# untitled.net
KiCad netlist of a schematic drawn in EAGLE
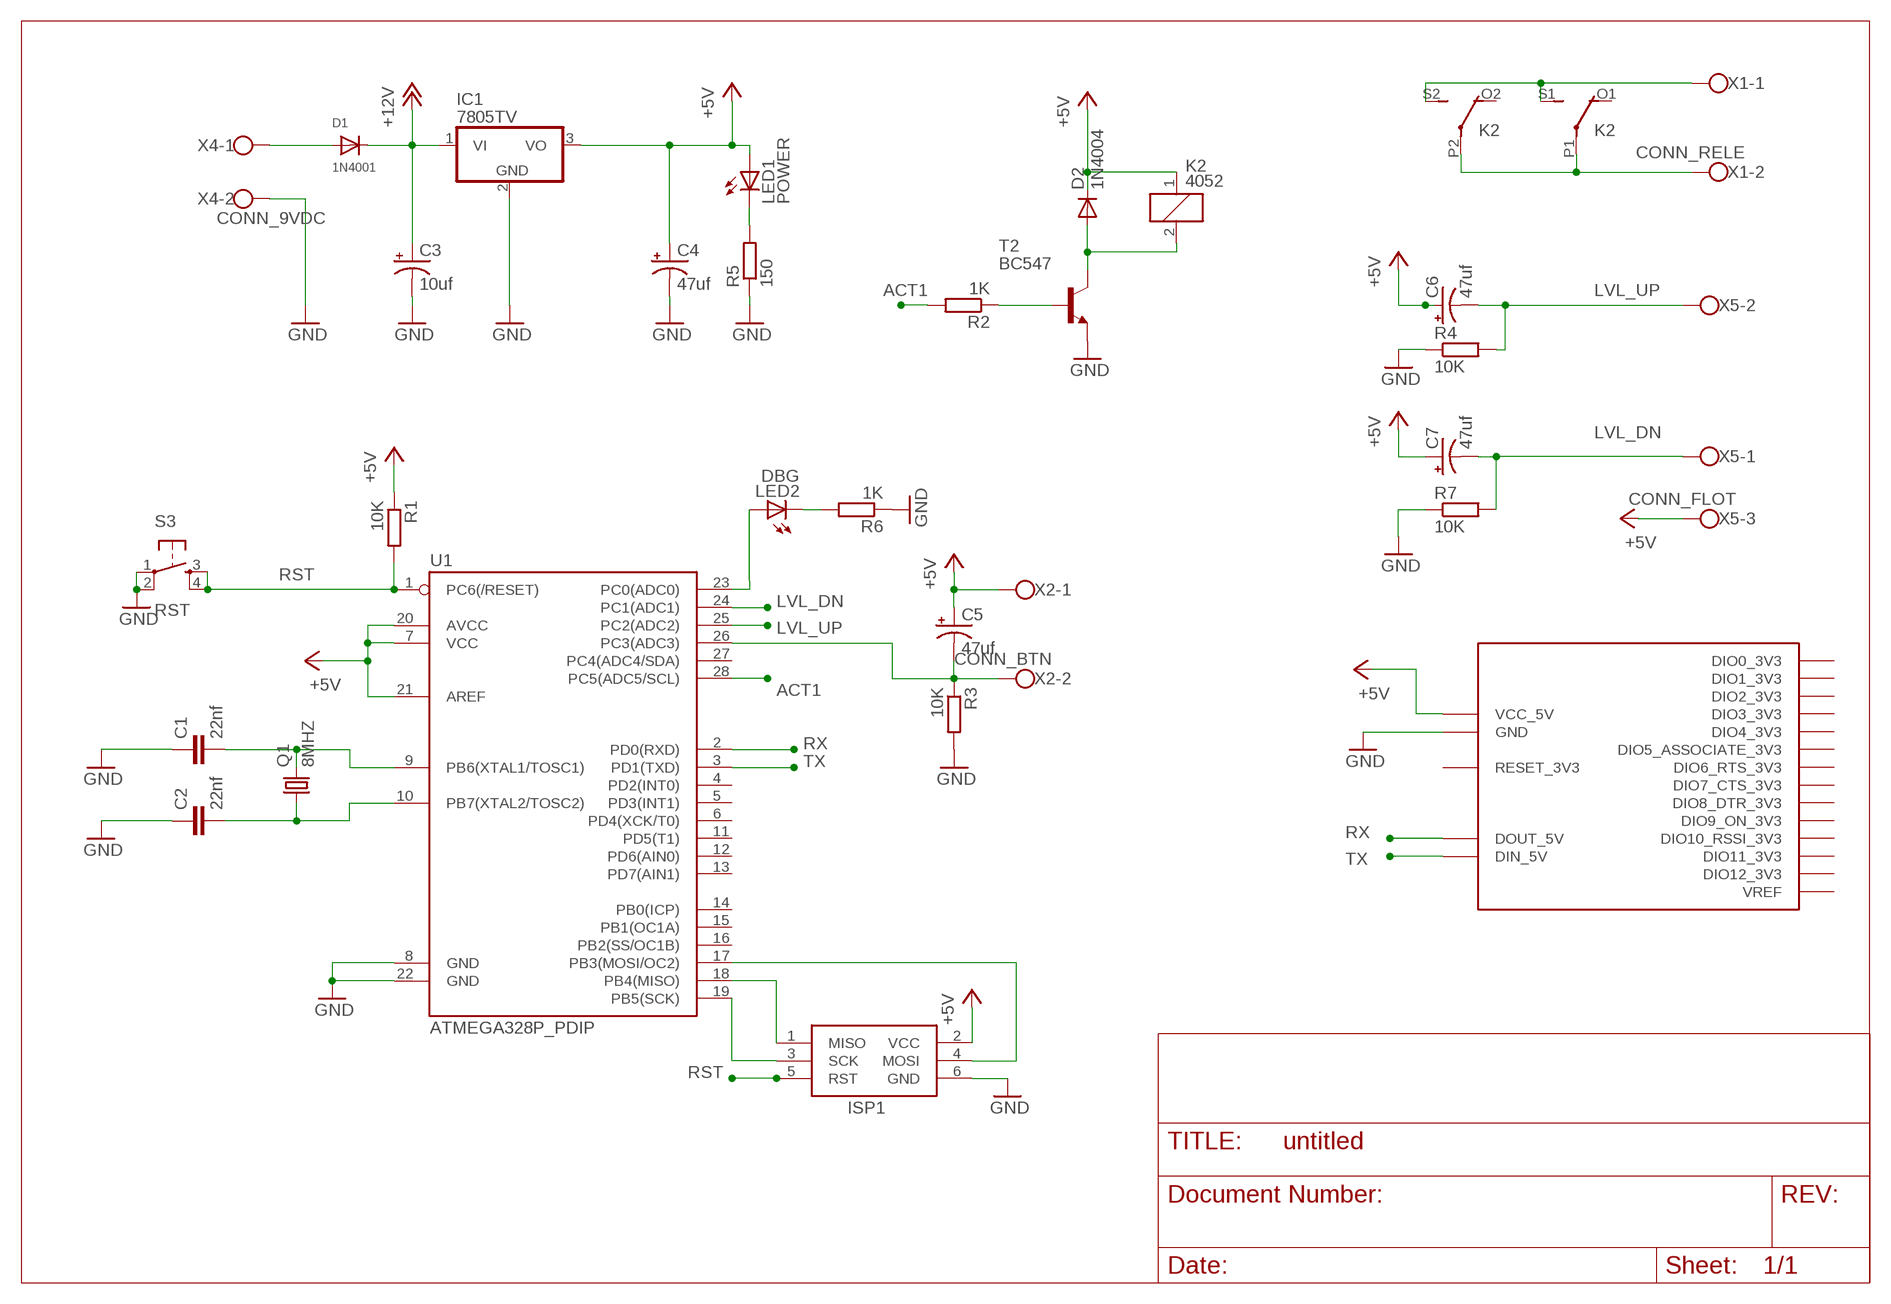
[diagram p0: schematic, sheet 1]

(export (version "E")
  (design (tool "Eeschema 10.0.6"))
  (components
    (comp (ref "C1")
      (value "22nf")
      (footprint "eagle-import:C2.5-3")
      (libsource (lib "eagle-import") (part "C2,5-3"))
    )
    (comp (ref "C2")
      (value "22nf")
      (footprint "eagle-import:C2.5-3")
      (libsource (lib "eagle-import") (part "C2,5-3"))
    )
    (comp (ref "C3")
      (value "10uf")
      (footprint "eagle-import:E2,5-6")
      (libsource (lib "eagle-import") (part "CPOL-USE2.5-6"))
    )
    (comp (ref "C4")
      (value "47uf")
      (footprint "eagle-import:E2,5-6")
      (libsource (lib "eagle-import") (part "CPOL-USE2.5-6"))
    )
    (comp (ref "C5")
      (value "47uf")
      (footprint "eagle-import:E2,5-6")
      (libsource (lib "eagle-import") (part "CPOL-USE2.5-6"))
    )
    (comp (ref "C6")
      (value "47uf")
      (footprint "eagle-import:E2,5-6")
      (libsource (lib "eagle-import") (part "CPOL-USE2.5-6"))
    )
    (comp (ref "C7")
      (value "47uf")
      (footprint "eagle-import:E2,5-6")
      (libsource (lib "eagle-import") (part "CPOL-USE2.5-6"))
    )
    (comp (ref "D1")
      (value "1N4001")
      (footprint "eagle-import:DO-1N4148")
      (libsource (lib "eagle-import") (part "DIODEDO-1N4148"))
    )
    (comp (ref "D2")
      (value "1N4004")
      (footprint "eagle-import:DO41-10")
      (libsource (lib "eagle-import") (part "1N4004"))
    )
    (comp (ref "IC1")
      (value "7805TV")
      (footprint "eagle-import:TO220V")
      (libsource (lib "eagle-import") (part "78TV05"))
    )
    (comp (ref "ISP1")
      (value "AVRISP-6")
      (footprint "eagle-import:AVRISP")
      (libsource (lib "eagle-import") (part "AVRISP-6"))
    )
    (comp (ref "K2")
      (value "4052")
      (footprint "eagle-import:F4052")
      (libsource (lib "eagle-import") (part "4052"))
    )
    (comp (ref "LED1")
      (value "POWER")
      (footprint "eagle-import:LED5MM")
      (libsource (lib "eagle-import") (part "LED5MM"))
    )
    (comp (ref "LED2")
      (value "DBG")
      (footprint "eagle-import:LED5MM")
      (libsource (lib "eagle-import") (part "LED5MM"))
    )
    (comp (ref "Q1")
      (value "8MHZ")
      (footprint "eagle-import:HC49U70")
      (libsource (lib "eagle-import") (part "CRYSTALHC49U70"))
    )
    (comp (ref "R1")
      (value "10K")
      (footprint "eagle-import:0207_10")
      (libsource (lib "eagle-import") (part "R-EU_0207/10"))
    )
    (comp (ref "R2")
      (value "1K")
      (footprint "eagle-import:0207_10")
      (libsource (lib "eagle-import") (part "R-EU_0207/10"))
    )
    (comp (ref "R3")
      (value "10K")
      (footprint "eagle-import:0207_10")
      (libsource (lib "eagle-import") (part "R-EU_0207/10"))
    )
    (comp (ref "R4")
      (value "10K")
      (footprint "eagle-import:0207_10")
      (libsource (lib "eagle-import") (part "R-EU_0207/10"))
    )
    (comp (ref "R5")
      (value "150")
      (footprint "eagle-import:0207_10")
      (libsource (lib "eagle-import") (part "R-EU_0207/10"))
    )
    (comp (ref "R6")
      (value "1K")
      (footprint "eagle-import:0207_10")
      (libsource (lib "eagle-import") (part "R-EU_0207/10"))
    )
    (comp (ref "R7")
      (value "10K")
      (footprint "eagle-import:0207_10")
      (libsource (lib "eagle-import") (part "R-EU_0207/10"))
    )
    (comp (ref "S3")
      (value "RST")
      (footprint "eagle-import:TACTILE-PTH")
      (libsource (lib "eagle-import") (part "TAC_SWITCHPTH"))
    )
    (comp (ref "T2")
      (value "BC547")
      (footprint "eagle-import:TO92-CBE")
      (libsource (lib "eagle-import") (part "-NPN-TO92-CBEBC547"))
    )
    (comp (ref "U$1")
      (value "XBEE_BREAKOUT_DIGOLE")
      (footprint "eagle-import:PDIP")
      (libsource (lib "eagle-import") (part "XBEE_BREAKOUT_DIGOLE"))
    )
    (comp (ref "U1")
      (value "ATMEGA328P_PDIP")
      (footprint "eagle-import:DIL28-3")
      (libsource (lib "eagle-import") (part "ATMEGA328P_PDIP"))
    )
    (comp (ref "X1")
      (value "CONN_RELE")
      (footprint "eagle-import:W237-102")
      (fields (field (name "MPN") "237-102"))
      (libsource (lib "eagle-import") (part "W237-102"))
    )
    (comp (ref "X2")
      (value "CONN_BTN")
      (footprint "eagle-import:W237-102")
      (fields (field (name "MPN") "237-102"))
      (libsource (lib "eagle-import") (part "W237-102"))
    )
    (comp (ref "X4")
      (value "CONN_9VDC")
      (footprint "eagle-import:W237-102")
      (fields (field (name "MPN") "237-102"))
      (libsource (lib "eagle-import") (part "W237-102"))
    )
    (comp (ref "X5")
      (value "CONN_FLOT")
      (footprint "eagle-import:W237-103")
      (fields (field (name "MPN") "237-103"))
      (libsource (lib "eagle-import") (part "W237-103"))
    )
  )
  (nets
    (net (code "1") (name "+5V") (class "Default")
      (node (ref "C4") (pin "+") (pinfunction "+_+") (pintype "passive"))
      (node (ref "C5") (pin "+") (pinfunction "+_+") (pintype "passive"))
      (node (ref "C6") (pin "+") (pinfunction "+_+") (pintype "passive"))
      (node (ref "C7") (pin "+") (pinfunction "+_+") (pintype "passive"))
      (node (ref "D2") (pin "C") (pinfunction "C_C") (pintype "passive"))
      (node (ref "IC1") (pin "3") (pinfunction "VO_3") (pintype "passive"))
      (node (ref "ISP1") (pin "2") (pinfunction "VCC_2") (pintype "power_in"))
      (node (ref "K2") (pin "1") (pinfunction "1_1") (pintype "passive"))
      (node (ref "LED1") (pin "A") (pinfunction "A_A") (pintype "passive"))
      (node (ref "R1") (pin "1") (pinfunction "1_1") (pintype "passive"))
      (node (ref "U$1") (pin "VCC_5V") (pinfunction "VCC_5V_VCC_5V") (pintype "bidirectional"))
      (node (ref "U1") (pin "20") (pinfunction "AVCC_20") (pintype "bidirectional"))
      (node (ref "U1") (pin "21") (pinfunction "AREF_21") (pintype "bidirectional"))
      (node (ref "U1") (pin "7") (pinfunction "VCC_7") (pintype "bidirectional"))
      (node (ref "X2") (pin "1") (pinfunction "KL_1") (pintype "passive"))
      (node (ref "X5") (pin "3") (pinfunction "KL_3") (pintype "passive"))
    )
    (net (code "2") (name "+12V") (class "Default")
      (node (ref "C3") (pin "+") (pinfunction "+_+") (pintype "passive"))
      (node (ref "D1") (pin "C") (pinfunction "C_C") (pintype "passive"))
      (node (ref "IC1") (pin "1") (pinfunction "VI_1") (pintype "input"))
    )
    (net (code "3") (name "/ACT1") (class "Default")
      (node (ref "R2") (pin "2") (pinfunction "2_2") (pintype "passive"))
      (node (ref "U1") (pin "28") (pinfunction "PC5(ADC5/SCL)_28") (pintype "bidirectional"))
    )
    (net (code "4") (name "/LVL_DN") (class "Default")
      (node (ref "C7") (pin "-") (pinfunction "-_-") (pintype "passive"))
      (node (ref "R7") (pin "2") (pinfunction "2_2") (pintype "passive"))
      (node (ref "U1") (pin "24") (pinfunction "PC1(ADC1)_24") (pintype "bidirectional"))
      (node (ref "X5") (pin "1") (pinfunction "KL_1") (pintype "passive"))
    )
    (net (code "5") (name "/LVL_UP") (class "Default")
      (node (ref "C6") (pin "-") (pinfunction "-_-") (pintype "passive"))
      (node (ref "R4") (pin "2") (pinfunction "2_2") (pintype "passive"))
      (node (ref "U1") (pin "25") (pinfunction "PC2(ADC2)_25") (pintype "bidirectional"))
      (node (ref "X5") (pin "2") (pinfunction "KL_2") (pintype "passive"))
    )
    (net (code "6") (name "/RST") (class "Default")
      (node (ref "ISP1") (pin "5") (pinfunction "RST_5") (pintype "output"))
      (node (ref "R1") (pin "2") (pinfunction "2_2") (pintype "passive"))
      (node (ref "S3") (pin "3") (pinfunction "3_3") (pintype "passive"))
      (node (ref "S3") (pin "4") (pinfunction "4_4") (pintype "passive"))
      (node (ref "U1") (pin "1") (pinfunction "PC6(/RESET)_1") (pintype "bidirectional"))
    )
    (net (code "7") (name "/RX") (class "Default")
      (node (ref "U$1") (pin "DOUT") (pinfunction "DOUT_5V_DOUT") (pintype "bidirectional"))
      (node (ref "U1") (pin "2") (pinfunction "PD0(RXD)_2") (pintype "bidirectional"))
    )
    (net (code "8") (name "/TX") (class "Default")
      (node (ref "U$1") (pin "DIN_5V") (pinfunction "DIN_5V_DIN_5V") (pintype "bidirectional"))
      (node (ref "U1") (pin "3") (pinfunction "PD1(TXD)_3") (pintype "bidirectional"))
    )
    (net (code "9") (name "GND") (class "Default")
      (node (ref "C1") (pin "1") (pinfunction "1_1") (pintype "passive"))
      (node (ref "C2") (pin "1") (pinfunction "1_1") (pintype "passive"))
      (node (ref "C3") (pin "-") (pinfunction "-_-") (pintype "passive"))
      (node (ref "C4") (pin "-") (pinfunction "-_-") (pintype "passive"))
      (node (ref "IC1") (pin "2") (pinfunction "GND_2") (pintype "passive"))
      (node (ref "ISP1") (pin "6") (pinfunction "GND_6") (pintype "power_in"))
      (node (ref "R3") (pin "2") (pinfunction "2_2") (pintype "passive"))
      (node (ref "R4") (pin "1") (pinfunction "1_1") (pintype "passive"))
      (node (ref "R5") (pin "1") (pinfunction "1_1") (pintype "passive"))
      (node (ref "R6") (pin "1") (pinfunction "1_1") (pintype "passive"))
      (node (ref "R7") (pin "1") (pinfunction "1_1") (pintype "passive"))
      (node (ref "S3") (pin "1") (pinfunction "1_1") (pintype "passive"))
      (node (ref "S3") (pin "2") (pinfunction "2_2") (pintype "passive"))
      (node (ref "T2") (pin "E") (pinfunction "E_E") (pintype "passive"))
      (node (ref "U$1") (pin "GND") (pinfunction "GND_GND") (pintype "bidirectional"))
      (node (ref "U1") (pin "22") (pinfunction "GND_22") (pintype "bidirectional"))
      (node (ref "U1") (pin "8") (pinfunction "GND_8") (pintype "bidirectional"))
      (node (ref "X4") (pin "2") (pinfunction "KL_2") (pintype "passive"))
    )
    (net (code "10") (name "Net-(D2-PadA)") (class "Default")
      (node (ref "D2") (pin "A") (pinfunction "A_A") (pintype "passive"))
      (node (ref "K2") (pin "2") (pinfunction "2_2") (pintype "passive"))
      (node (ref "T2") (pin "C") (pinfunction "C_C") (pintype "passive"))
    )
    (net (code "11") (name "Net-(ISP1-MISO)") (class "Default")
      (node (ref "ISP1") (pin "1") (pinfunction "MISO_1") (pintype "input"))
      (node (ref "U1") (pin "18") (pinfunction "PB4(MISO)_18") (pintype "bidirectional"))
    )
    (net (code "12") (name "Net-(ISP1-MOSI)") (class "Default")
      (node (ref "ISP1") (pin "4") (pinfunction "MOSI_4") (pintype "output"))
      (node (ref "U1") (pin "17") (pinfunction "PB3(MOSI/OC2)_17") (pintype "bidirectional"))
    )
    (net (code "13") (name "Net-(ISP1-SCK)") (class "Default")
      (node (ref "ISP1") (pin "3") (pinfunction "SCK_3") (pintype "output"))
      (node (ref "U1") (pin "19") (pinfunction "PB5(SCK)_19") (pintype "bidirectional"))
    )
    (net (code "14") (name "Net-(K2B-P)") (class "Default")
      (node (ref "K2") (pin "P1") (pinfunction "P_P1") (pintype "passive"))
      (node (ref "K2") (pin "P2") (pinfunction "P_P2") (pintype "passive"))
      (node (ref "X1") (pin "2") (pinfunction "KL_2") (pintype "passive"))
    )
    (net (code "15") (name "Net-(K2B-S)") (class "Default")
      (node (ref "K2") (pin "S1") (pinfunction "S_S1") (pintype "passive"))
      (node (ref "K2") (pin "S2") (pinfunction "S_S2") (pintype "passive"))
      (node (ref "X1") (pin "1") (pinfunction "KL_1") (pintype "passive"))
    )
    (net (code "16") (name "Net-(LED1-C)") (class "Default")
      (node (ref "LED1") (pin "K") (pinfunction "C_K") (pintype "passive"))
      (node (ref "R5") (pin "2") (pinfunction "2_2") (pintype "passive"))
    )
    (net (code "17") (name "Net-(LED2-C)") (class "Default")
      (node (ref "LED2") (pin "K") (pinfunction "C_K") (pintype "passive"))
      (node (ref "R6") (pin "2") (pinfunction "2_2") (pintype "passive"))
    )
    (net (code "18") (name "Net-(R2-Pad1)") (class "Default")
      (node (ref "R2") (pin "1") (pinfunction "1_1") (pintype "passive"))
      (node (ref "T2") (pin "B") (pinfunction "B_B") (pintype "passive"))
    )
    (net (code "19") (name "Net-(U1-PB6(XTAL1{slash}TOSC1))") (class "Default")
      (node (ref "C1") (pin "2") (pinfunction "2_2") (pintype "passive"))
      (node (ref "Q1") (pin "2") (pinfunction "2_2") (pintype "passive"))
      (node (ref "U1") (pin "9") (pinfunction "PB6(XTAL1/TOSC1)_9") (pintype "bidirectional"))
    )
    (net (code "20") (name "Net-(U1-PB7(XTAL2{slash}TOSC2))") (class "Default")
      (node (ref "C2") (pin "2") (pinfunction "2_2") (pintype "passive"))
      (node (ref "Q1") (pin "1") (pinfunction "1_1") (pintype "passive"))
      (node (ref "U1") (pin "10") (pinfunction "PB7(XTAL2/TOSC2)_10") (pintype "bidirectional"))
    )
    (net (code "21") (name "Net-(U1-PC0(ADC0))") (class "Default")
      (node (ref "LED2") (pin "A") (pinfunction "A_A") (pintype "passive"))
      (node (ref "U1") (pin "23") (pinfunction "PC0(ADC0)_23") (pintype "bidirectional"))
    )
    (net (code "22") (name "Net-(U1-PC3(ADC3))") (class "Default")
      (node (ref "C5") (pin "-") (pinfunction "-_-") (pintype "passive"))
      (node (ref "R3") (pin "1") (pinfunction "1_1") (pintype "passive"))
      (node (ref "U1") (pin "26") (pinfunction "PC3(ADC3)_26") (pintype "bidirectional"))
      (node (ref "X2") (pin "2") (pinfunction "KL_2") (pintype "passive"))
    )
    (net (code "23") (name "Net-(X4A-KL)") (class "Default")
      (node (ref "D1") (pin "A") (pinfunction "A_A") (pintype "passive"))
      (node (ref "X4") (pin "1") (pinfunction "KL_1") (pintype "passive"))
    )
    (net (code "24") (name "unconnected-(K2B-O-PadO1)") (class "Default")
      (node (ref "K2") (pin "O1") (pinfunction "O_O1") (pintype "passive"))
    )
    (net (code "25") (name "unconnected-(K2C-O-PadO2)") (class "Default")
      (node (ref "K2") (pin "O2") (pinfunction "O_O2") (pintype "passive"))
    )
    (net (code "26") (name "unconnected-(U$1-DIO5_ASSOCIATE_3V3-PadASSOCIATE_3V3)") (class "Default")
      (node (ref "U$1") (pin "ASSOCIATE_3V3") (pinfunction "DIO5_ASSOCIATE_3V3_ASSOCIATE_3V3") (pintype "bidirectional"))
    )
    (net (code "27") (name "unconnected-(U$1-DIO6_RTS_3V3-PadRTS_3V3)") (class "Default")
      (node (ref "U$1") (pin "RTS_3V3") (pinfunction "DIO6_RTS_3V3_RTS_3V3") (pintype "bidirectional"))
    )
    (net (code "28") (name "unconnected-(U$1-DIO7_CTS_3V3-PadCTS_3V3)") (class "Default")
      (node (ref "U$1") (pin "CTS_3V3") (pinfunction "DIO7_CTS_3V3_CTS_3V3") (pintype "bidirectional"))
    )
    (net (code "29") (name "unconnected-(U$1-DIO8_DTR_3V3-PadDTR_3V3)") (class "Default")
      (node (ref "U$1") (pin "DTR_3V3") (pinfunction "DIO8_DTR_3V3_DTR_3V3") (pintype "bidirectional"))
    )
    (net (code "30") (name "unconnected-(U$1-DIO9_ON_3V3-PadON_3V3)") (class "Default")
      (node (ref "U$1") (pin "ON_3V3") (pinfunction "DIO9_ON_3V3_ON_3V3") (pintype "bidirectional"))
    )
    (net (code "31") (name "unconnected-(U$1-DIO10_RSSI_3V3-PadRSSI_3V3)") (class "Default")
      (node (ref "U$1") (pin "RSSI_3V3") (pinfunction "DIO10_RSSI_3V3_RSSI_3V3") (pintype "bidirectional"))
    )
    (net (code "32") (name "unconnected-(U$1-PadDIO0_3V3)") (class "Default")
      (node (ref "U$1") (pin "DIO0_3V3") (pinfunction "DIO0_3V3_DIO0_3V3") (pintype "bidirectional"))
    )
    (net (code "33") (name "unconnected-(U$1-PadDIO1_3V3)") (class "Default")
      (node (ref "U$1") (pin "DIO1_3V3") (pinfunction "DIO1_3V3_DIO1_3V3") (pintype "bidirectional"))
    )
    (net (code "34") (name "unconnected-(U$1-PadDIO2_3V3)") (class "Default")
      (node (ref "U$1") (pin "DIO2_3V3") (pinfunction "DIO2_3V3_DIO2_3V3") (pintype "bidirectional"))
    )
    (net (code "35") (name "unconnected-(U$1-PadDIO3_3V3)") (class "Default")
      (node (ref "U$1") (pin "DIO3_3V3") (pinfunction "DIO3_3V3_DIO3_3V3") (pintype "bidirectional"))
    )
    (net (code "36") (name "unconnected-(U$1-PadDIO4_3V3)") (class "Default")
      (node (ref "U$1") (pin "DIO4_3V3") (pinfunction "DIO4_3V3_DIO4_3V3") (pintype "bidirectional"))
    )
    (net (code "37") (name "unconnected-(U$1-PadDIO11_3V3)") (class "Default")
      (node (ref "U$1") (pin "DIO11_3V3") (pinfunction "DIO11_3V3_DIO11_3V3") (pintype "bidirectional"))
    )
    (net (code "38") (name "unconnected-(U$1-PadDIO12_3V3)") (class "Default")
      (node (ref "U$1") (pin "DIO12_3V3") (pinfunction "DIO12_3V3_DIO12_3V3") (pintype "bidirectional"))
    )
    (net (code "39") (name "unconnected-(U$1-PadRESET_3V3)") (class "Default")
      (node (ref "U$1") (pin "RESET_3V3") (pinfunction "RESET_3V3_RESET_3V3") (pintype "bidirectional"))
    )
    (net (code "40") (name "unconnected-(U$1-VREF-PadVREF_3V3)") (class "Default")
      (node (ref "U$1") (pin "VREF_3V3") (pinfunction "VREF_VREF_3V3") (pintype "bidirectional"))
    )
    (net (code "41") (name "unconnected-(U1-PB0(ICP)-Pad14)") (class "Default")
      (node (ref "U1") (pin "14") (pinfunction "PB0(ICP)_14") (pintype "bidirectional"))
    )
    (net (code "42") (name "unconnected-(U1-PB1(OC1A)-Pad15)") (class "Default")
      (node (ref "U1") (pin "15") (pinfunction "PB1(OC1A)_15") (pintype "bidirectional"))
    )
    (net (code "43") (name "unconnected-(U1-PB2(SS{slash}OC1B)-Pad16)") (class "Default")
      (node (ref "U1") (pin "16") (pinfunction "PB2(SS/OC1B)_16") (pintype "bidirectional"))
    )
    (net (code "44") (name "unconnected-(U1-PC4(ADC4{slash}SDA)-Pad27)") (class "Default")
      (node (ref "U1") (pin "27") (pinfunction "PC4(ADC4/SDA)_27") (pintype "bidirectional"))
    )
    (net (code "45") (name "unconnected-(U1-PD2(INT0)-Pad4)") (class "Default")
      (node (ref "U1") (pin "4") (pinfunction "PD2(INT0)_4") (pintype "bidirectional"))
    )
    (net (code "46") (name "unconnected-(U1-PD3(INT1)-Pad5)") (class "Default")
      (node (ref "U1") (pin "5") (pinfunction "PD3(INT1)_5") (pintype "bidirectional"))
    )
    (net (code "47") (name "unconnected-(U1-PD4(XCK{slash}T0)-Pad6)") (class "Default")
      (node (ref "U1") (pin "6") (pinfunction "PD4(XCK/T0)_6") (pintype "bidirectional"))
    )
    (net (code "48") (name "unconnected-(U1-PD5(T1)-Pad11)") (class "Default")
      (node (ref "U1") (pin "11") (pinfunction "PD5(T1)_11") (pintype "bidirectional"))
    )
    (net (code "49") (name "unconnected-(U1-PD6(AIN0)-Pad12)") (class "Default")
      (node (ref "U1") (pin "12") (pinfunction "PD6(AIN0)_12") (pintype "bidirectional"))
    )
    (net (code "50") (name "unconnected-(U1-PD7(AIN1)-Pad13)") (class "Default")
      (node (ref "U1") (pin "13") (pinfunction "PD7(AIN1)_13") (pintype "bidirectional"))
    )
  )
)
